# stm32-2inch40-usb-sd-proto.net
KiCad netlist of a schematic drawn in EAGLE
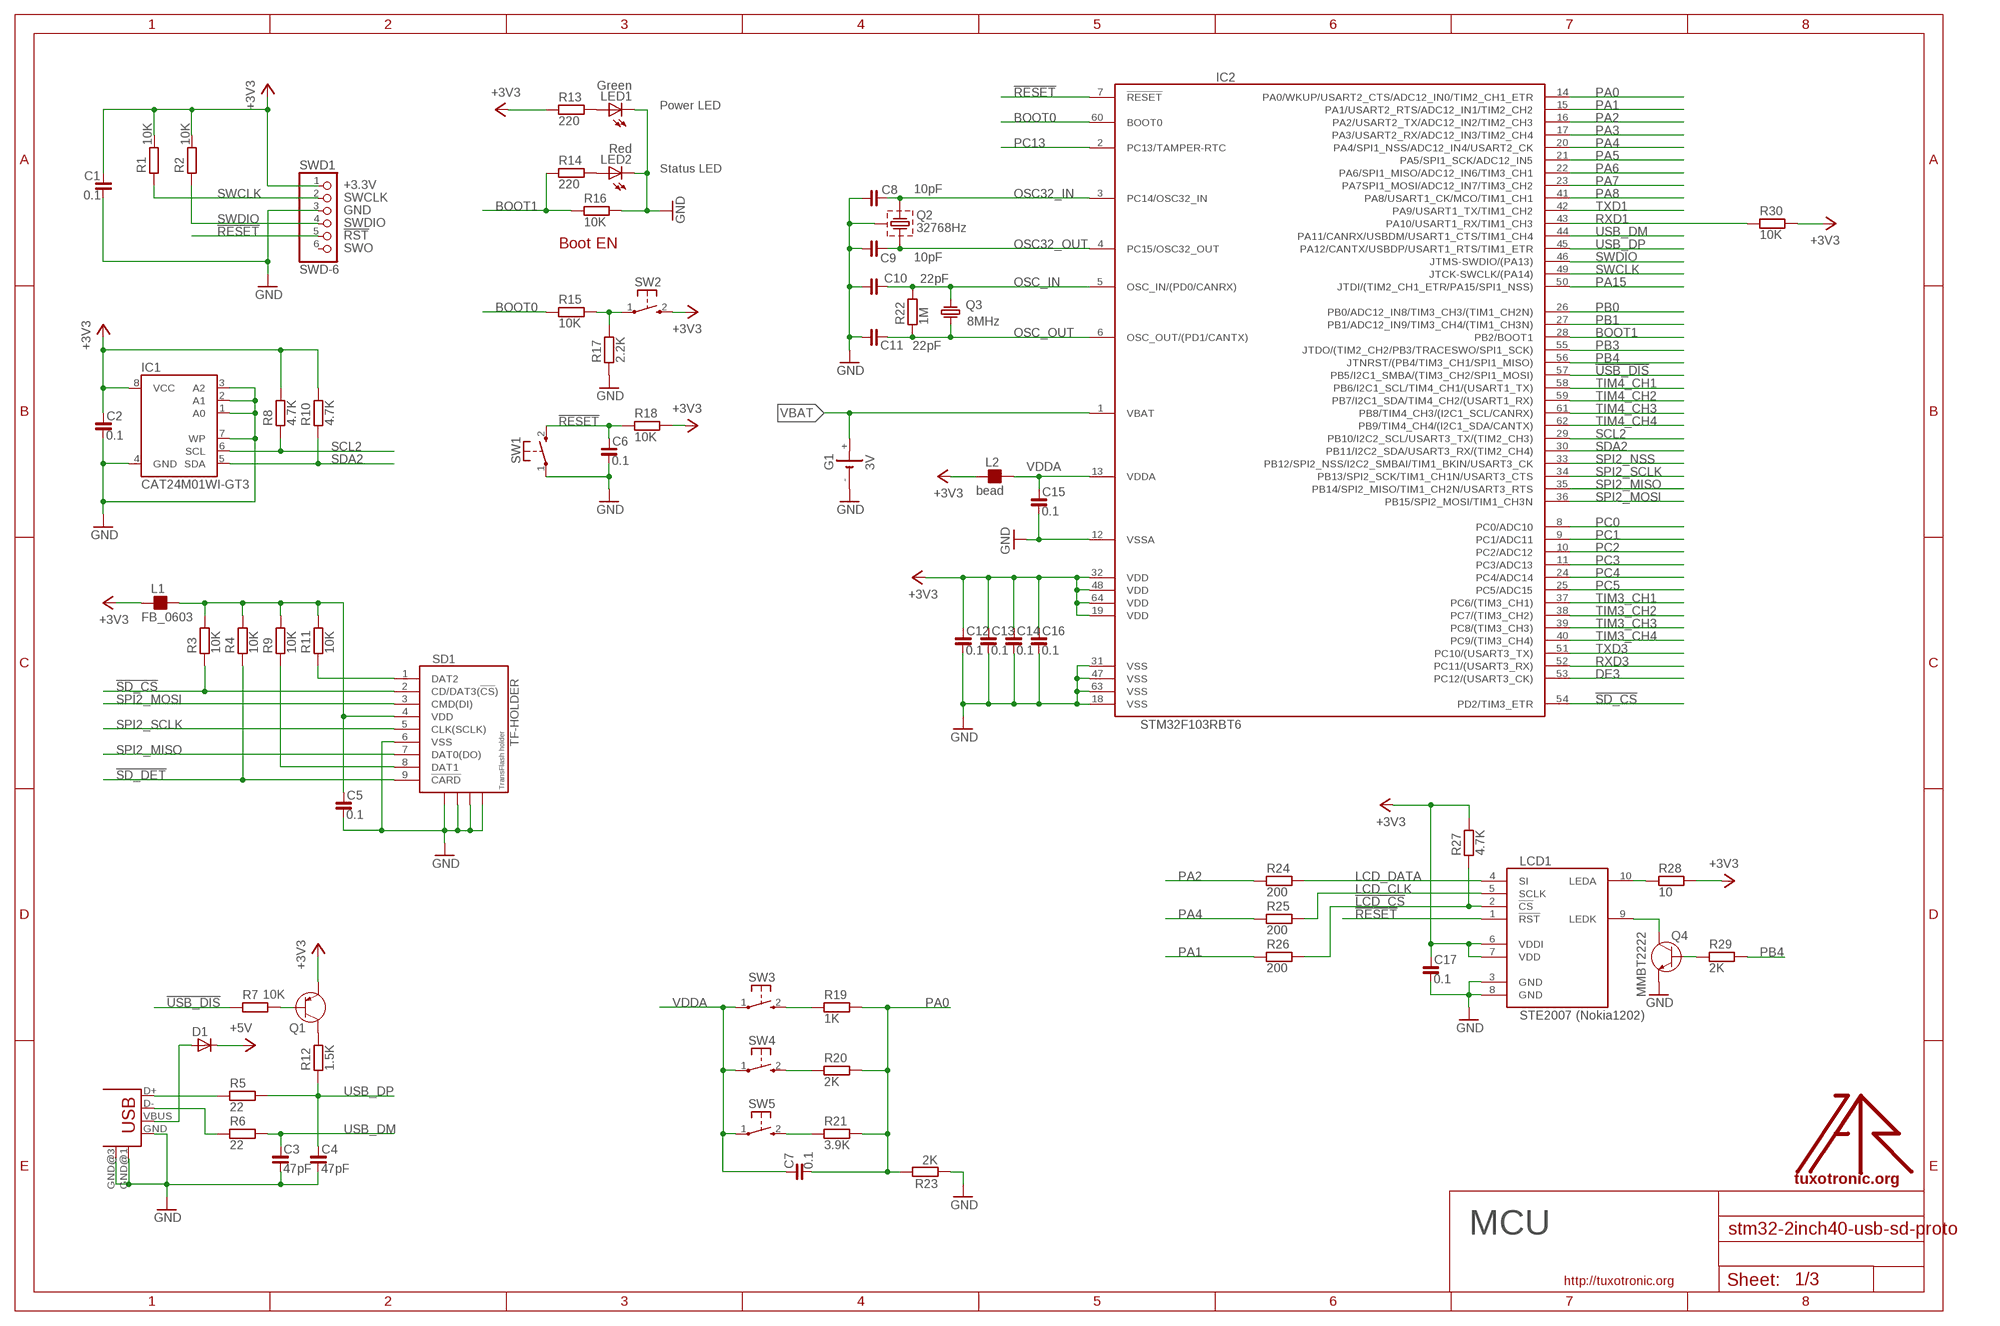
[diagram p0: schematic, sheet 1]
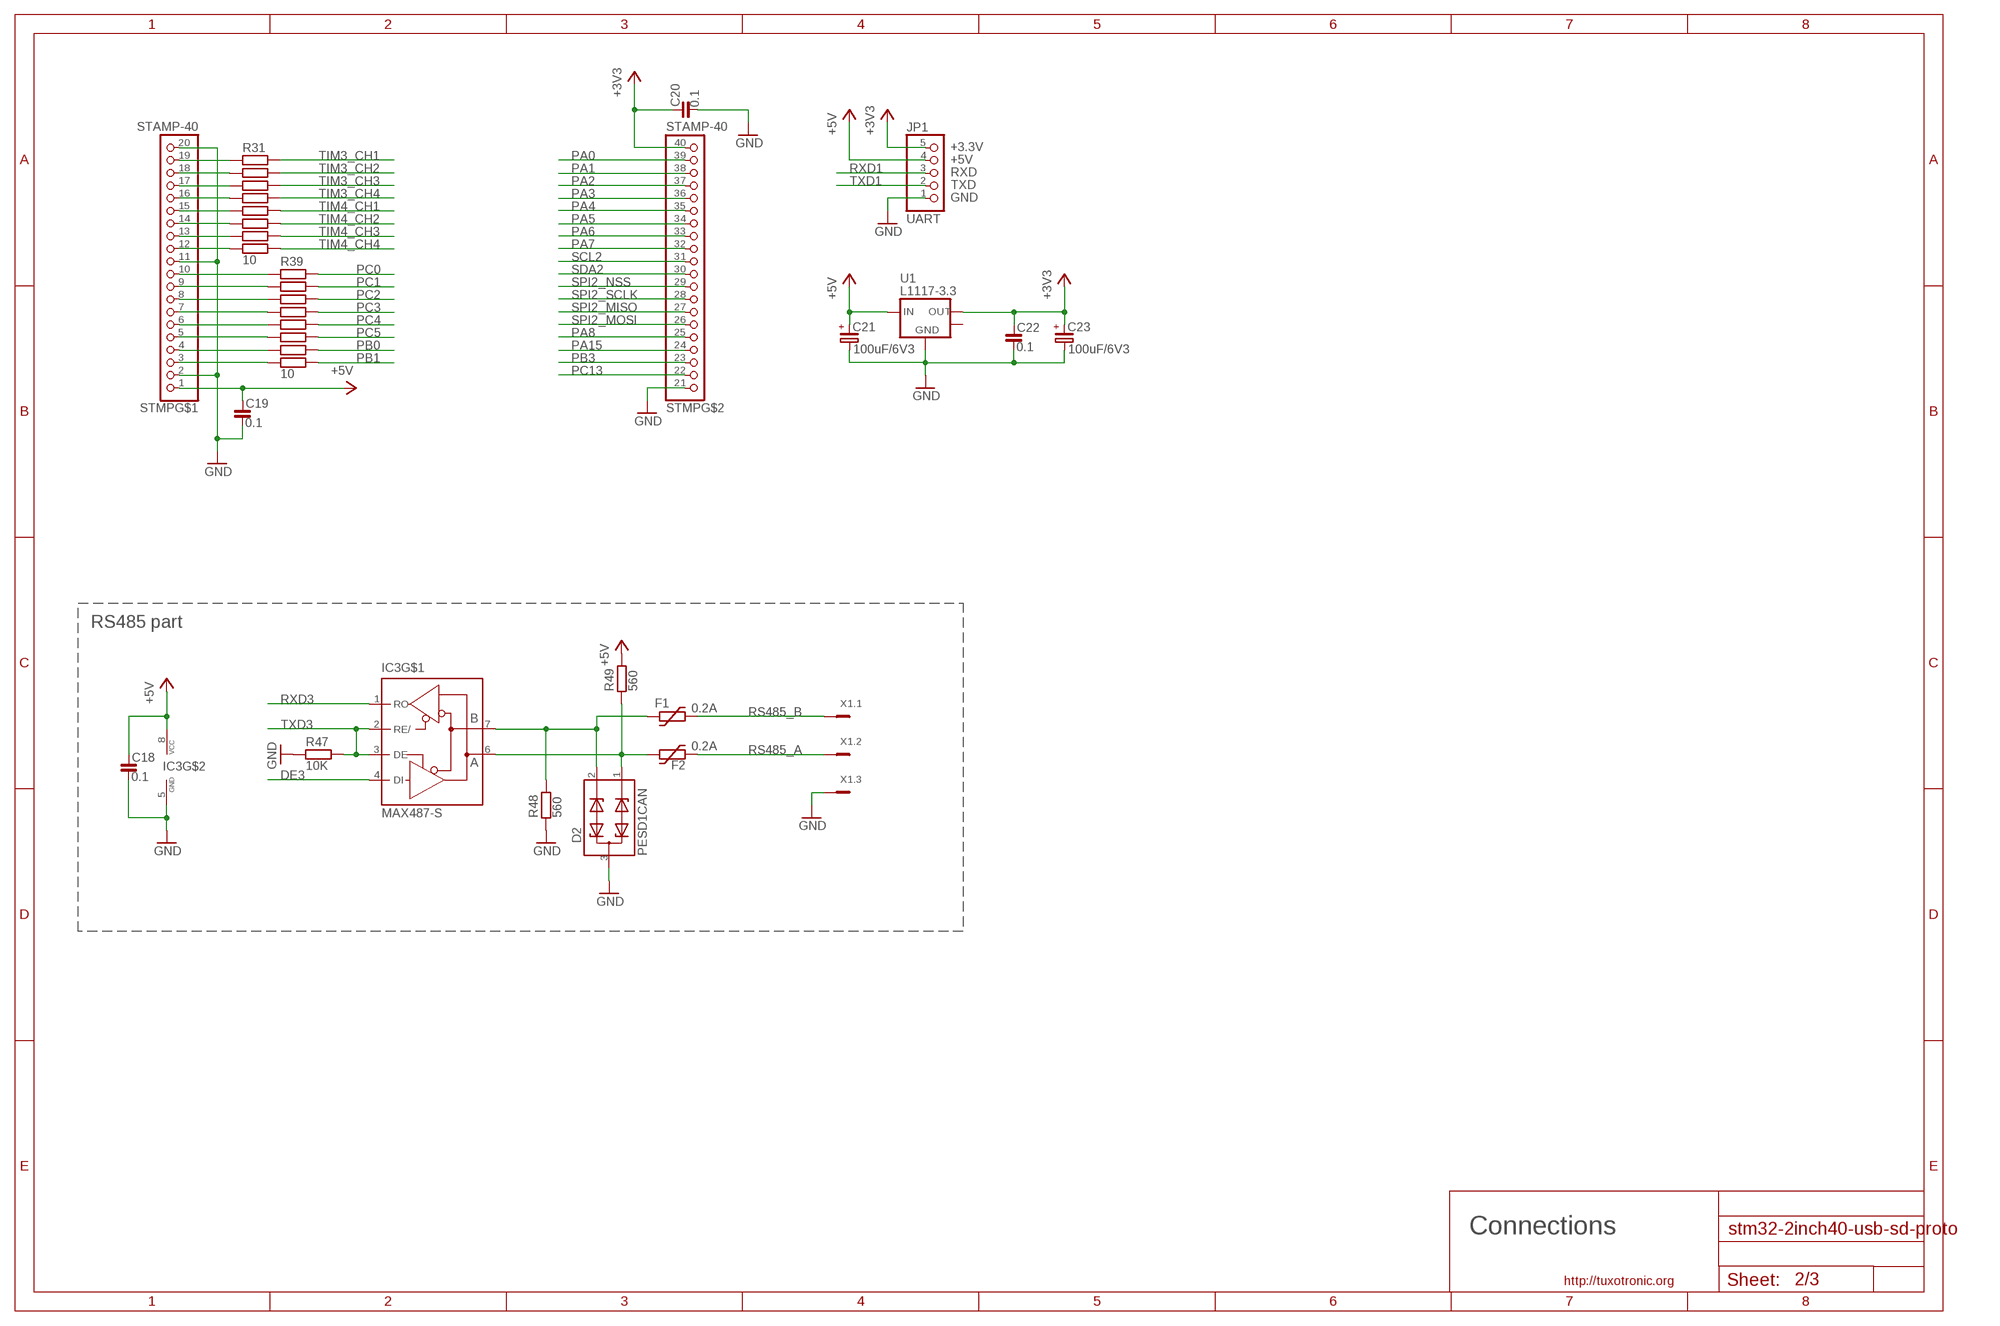
[diagram p1: schematic, sheet 2]
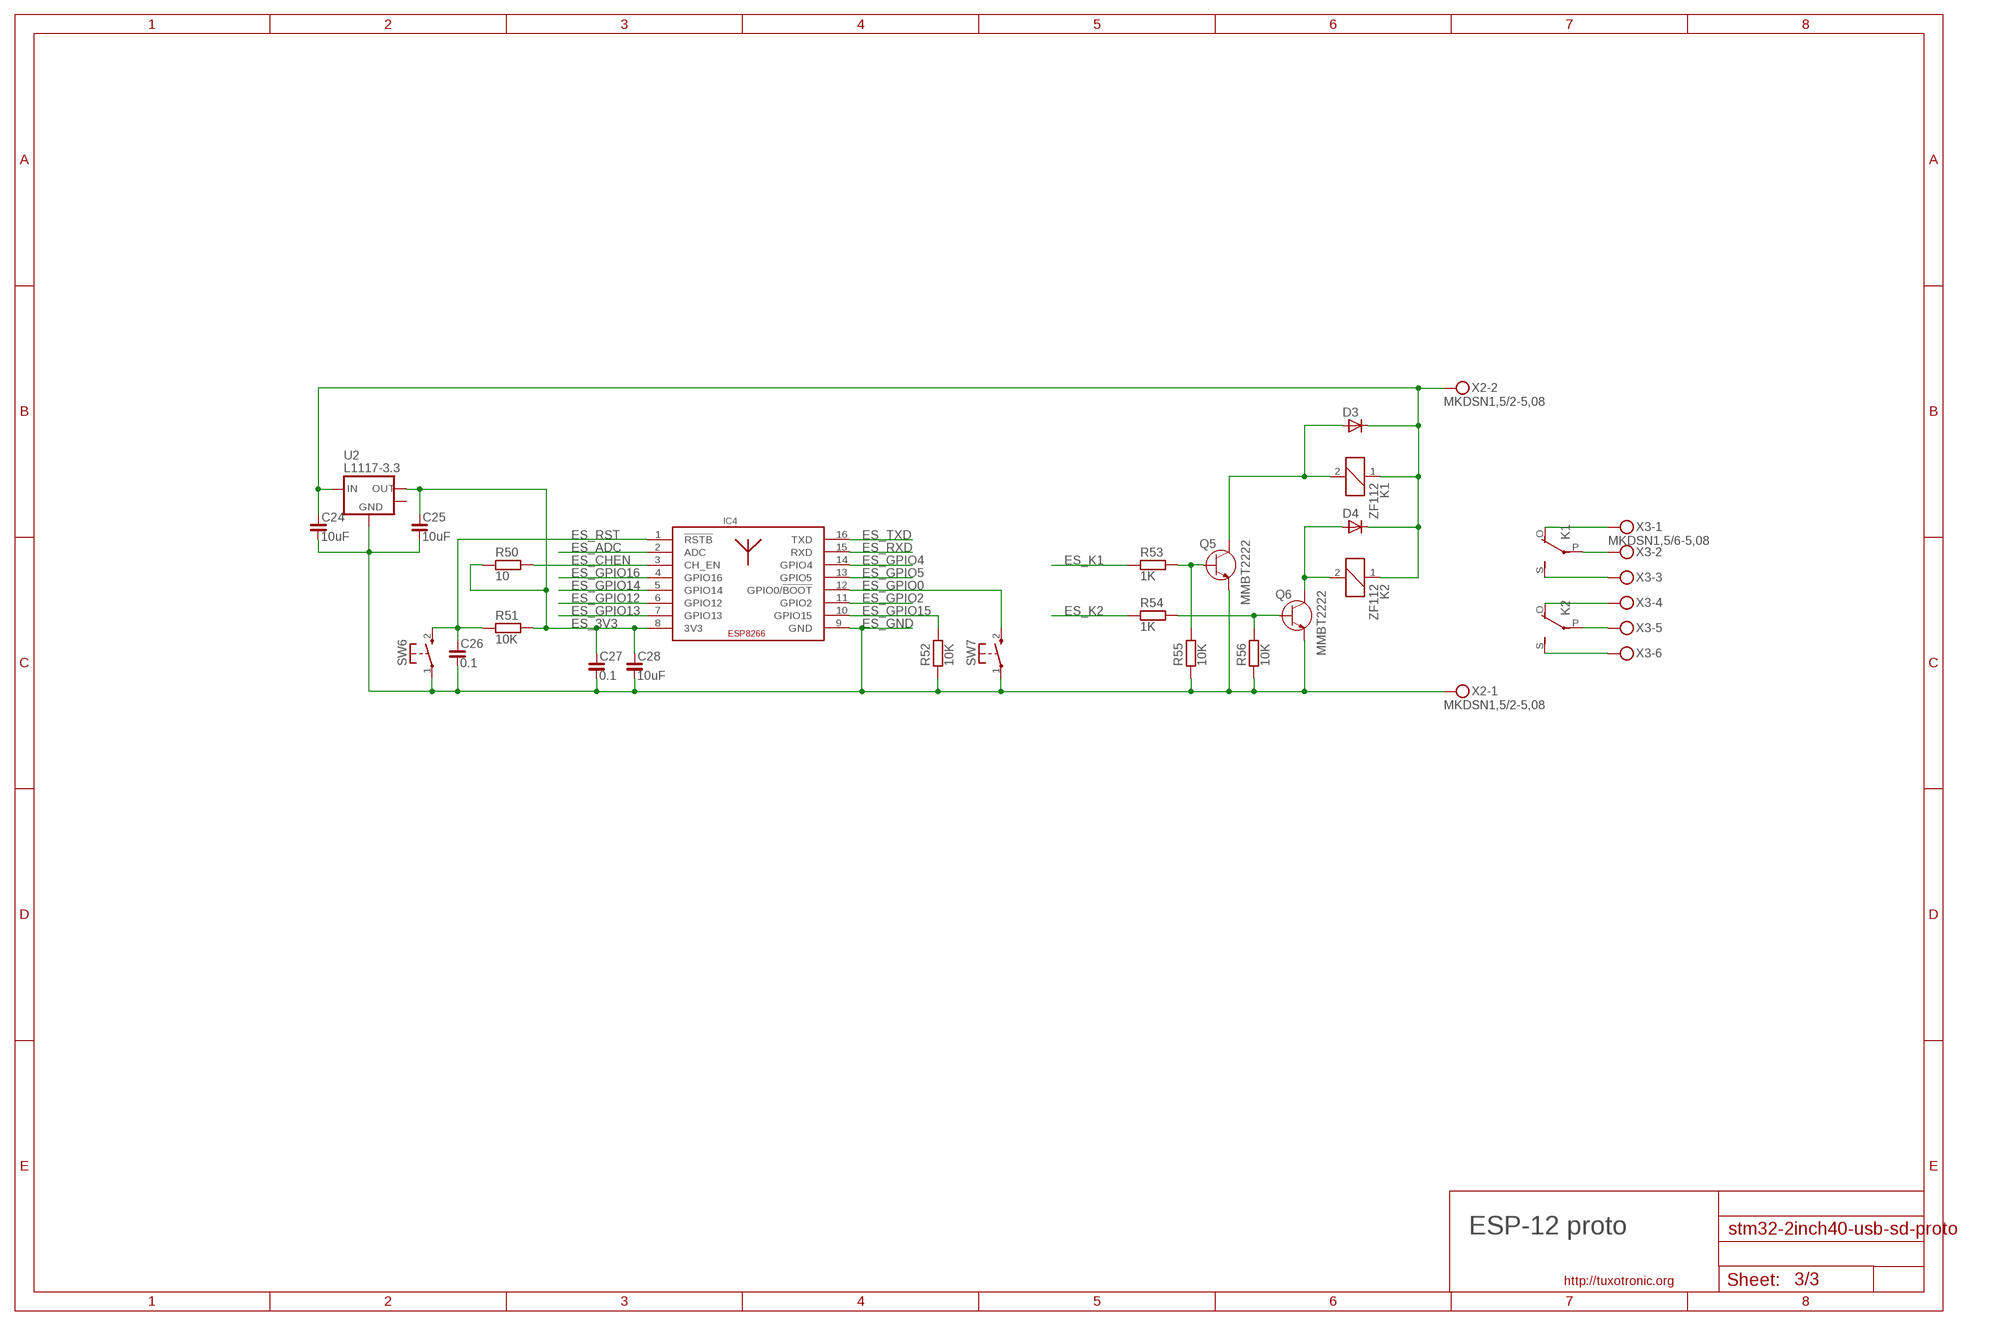
[diagram p2: schematic, sheet 3]

(export (version "E")
  (design (tool "Eeschema 10.0.6"))
  (components
    (comp (ref "C24")
      (value "10uF")
      (footprint "eagle-import:C0805")
      (libsource (lib "eagle-import") (part "C_0805"))
    )
    (comp (ref "C25")
      (value "10uF")
      (footprint "eagle-import:C0805")
      (libsource (lib "eagle-import") (part "C_0805"))
    )
    (comp (ref "C26")
      (value "0.1")
      (footprint "eagle-import:C0805")
      (libsource (lib "eagle-import") (part "C_0805"))
    )
    (comp (ref "C27")
      (value "0.1")
      (footprint "eagle-import:C0805")
      (libsource (lib "eagle-import") (part "C_0805"))
    )
    (comp (ref "C28")
      (value "10uF")
      (footprint "eagle-import:C0805")
      (libsource (lib "eagle-import") (part "C_0805"))
    )
    (comp (ref "D3")
      (value "D-SOD-80")
      (footprint "eagle-import:SOD80")
      (libsource (lib "eagle-import") (part "D-SOD-80"))
    )
    (comp (ref "D4")
      (value "D-SOD-80")
      (footprint "eagle-import:SOD80")
      (libsource (lib "eagle-import") (part "D-SOD-80"))
    )
    (comp (ref "IC4")
      (value "ESP-12")
      (footprint "eagle-import:ESP12")
      (libsource (lib "eagle-import") (part "ESP-12"))
    )
    (comp (ref "K1")
      (value "ZF112")
      (footprint "eagle-import:ZF112")
      (libsource (lib "eagle-import") (part "ZF112"))
    )
    (comp (ref "K2")
      (value "ZF112")
      (footprint "eagle-import:ZF112")
      (libsource (lib "eagle-import") (part "ZF112"))
    )
    (comp (ref "Q5")
      (value "MMBT2222")
      (footprint "eagle-import:SOT23")
      (libsource (lib "eagle-import") (part "MMBT2222"))
    )
    (comp (ref "Q6")
      (value "MMBT2222")
      (footprint "eagle-import:SOT23")
      (libsource (lib "eagle-import") (part "MMBT2222"))
    )
    (comp (ref "R50")
      (value "10")
      (footprint "eagle-import:R0805")
      (libsource (lib "eagle-import") (part "R_0805"))
    )
    (comp (ref "R51")
      (value "10K")
      (footprint "eagle-import:R0805")
      (libsource (lib "eagle-import") (part "R_0805"))
    )
    (comp (ref "R52")
      (value "10K")
      (footprint "eagle-import:R0805")
      (libsource (lib "eagle-import") (part "R_0805"))
    )
    (comp (ref "R53")
      (value "1K")
      (footprint "eagle-import:R0805")
      (libsource (lib "eagle-import") (part "R_0805"))
    )
    (comp (ref "R54")
      (value "1K")
      (footprint "eagle-import:R0805")
      (libsource (lib "eagle-import") (part "R_0805"))
    )
    (comp (ref "R55")
      (value "10K")
      (footprint "eagle-import:R0805")
      (libsource (lib "eagle-import") (part "R_0805"))
    )
    (comp (ref "R56")
      (value "10K")
      (footprint "eagle-import:R0805")
      (libsource (lib "eagle-import") (part "R_0805"))
    )
    (comp (ref "SW6")
      (value "KSS-2EG4430")
      (footprint "eagle-import:KSS-2EG4430")
      (libsource (lib "eagle-import") (part "KSS-2EG4430"))
    )
    (comp (ref "SW7")
      (value "KSS-2EG4430")
      (footprint "eagle-import:KSS-2EG4430")
      (libsource (lib "eagle-import") (part "KSS-2EG4430"))
    )
    (comp (ref "U2")
      (value "L1117-3.3")
      (footprint "eagle-import:SOT223")
      (libsource (lib "eagle-import") (part "LM1117-3.3"))
    )
    (comp (ref "X2")
      (value "MKDSN1,5/2-5,08")
      (footprint "eagle-import:MKDSN1,5_2-5,08")
      (libsource (lib "eagle-import") (part "MKDSN1,5/2-5,08"))
    )
    (comp (ref "X3")
      (value "MKDSN1,5/6-5,08")
      (footprint "eagle-import:MKDSN1,5_6-5,08")
      (libsource (lib "eagle-import") (part "MKDSN1,5/6-5,08"))
    )
    (comp (ref "C18")
      (value "0.1")
      (footprint "eagle-import:C0603")
      (libsource (lib "eagle-import") (part "C_0603"))
    )
    (comp (ref "C19")
      (value "0.1")
      (footprint "eagle-import:C0805")
      (libsource (lib "eagle-import") (part "C_0805"))
    )
    (comp (ref "C20")
      (value "0.1")
      (footprint "eagle-import:C0805")
      (libsource (lib "eagle-import") (part "C_0805"))
    )
    (comp (ref "C21")
      (value "100uF/6V3")
      (footprint "eagle-import:SMC_D")
      (libsource (lib "eagle-import") (part "CP_SMCD"))
    )
    (comp (ref "C22")
      (value "0.1")
      (footprint "eagle-import:C0805")
      (libsource (lib "eagle-import") (part "C_0805"))
    )
    (comp (ref "C23")
      (value "100uF/6V3")
      (footprint "eagle-import:SMC_D")
      (libsource (lib "eagle-import") (part "CP_SMCD"))
    )
    (comp (ref "D2")
      (value "PESD1CAN")
      (footprint "eagle-import:SOT23")
      (libsource (lib "eagle-import") (part "PESD1CAN"))
    )
    (comp (ref "F1")
      (value "0.2A")
      (footprint "eagle-import:1206L")
      (libsource (lib "eagle-import") (part "1206L"))
    )
    (comp (ref "F2")
      (value "0.2A")
      (footprint "eagle-import:1206L")
      (libsource (lib "eagle-import") (part "1206L"))
    )
    (comp (ref "IC3")
      (value "MAX487-S")
      (footprint "eagle-import:SO08")
      (libsource (lib "eagle-import") (part "MAX487-S"))
    )
    (comp (ref "JP1")
      (value "UART")
      (footprint "eagle-import:UART_1X05")
      (libsource (lib "eagle-import") (part "UART-5_2.54"))
    )
    (comp (ref "R31")
      (value "10")
      (footprint "eagle-import:R0603")
      (libsource (lib "eagle-import") (part "R_0603"))
    )
    (comp (ref "R32")
      (value "10")
      (footprint "eagle-import:R0603")
      (libsource (lib "eagle-import") (part "R_0603"))
    )
    (comp (ref "R33")
      (value "10")
      (footprint "eagle-import:R0603")
      (libsource (lib "eagle-import") (part "R_0603"))
    )
    (comp (ref "R34")
      (value "10")
      (footprint "eagle-import:R0603")
      (libsource (lib "eagle-import") (part "R_0603"))
    )
    (comp (ref "R35")
      (value "10")
      (footprint "eagle-import:R0603")
      (libsource (lib "eagle-import") (part "R_0603"))
    )
    (comp (ref "R36")
      (value "10")
      (footprint "eagle-import:R0603")
      (libsource (lib "eagle-import") (part "R_0603"))
    )
    (comp (ref "R37")
      (value "10")
      (footprint "eagle-import:R0603")
      (libsource (lib "eagle-import") (part "R_0603"))
    )
    (comp (ref "R38")
      (value "10")
      (footprint "eagle-import:R0603")
      (libsource (lib "eagle-import") (part "R_0603"))
    )
    (comp (ref "R39")
      (value "10")
      (footprint "eagle-import:R0603")
      (libsource (lib "eagle-import") (part "R_0603"))
    )
    (comp (ref "R40")
      (value "10")
      (footprint "eagle-import:R0603")
      (libsource (lib "eagle-import") (part "R_0603"))
    )
    (comp (ref "R41")
      (value "10")
      (footprint "eagle-import:R0603")
      (libsource (lib "eagle-import") (part "R_0603"))
    )
    (comp (ref "R42")
      (value "10")
      (footprint "eagle-import:R0603")
      (libsource (lib "eagle-import") (part "R_0603"))
    )
    (comp (ref "R43")
      (value "10")
      (footprint "eagle-import:R0603")
      (libsource (lib "eagle-import") (part "R_0603"))
    )
    (comp (ref "R44")
      (value "10")
      (footprint "eagle-import:R0603")
      (libsource (lib "eagle-import") (part "R_0603"))
    )
    (comp (ref "R45")
      (value "10")
      (footprint "eagle-import:R0603")
      (libsource (lib "eagle-import") (part "R_0603"))
    )
    (comp (ref "R46")
      (value "10")
      (footprint "eagle-import:R0603")
      (libsource (lib "eagle-import") (part "R_0603"))
    )
    (comp (ref "R47")
      (value "10K")
      (footprint "eagle-import:R0603")
      (libsource (lib "eagle-import") (part "R_0603"))
    )
    (comp (ref "R48")
      (value "560")
      (footprint "eagle-import:R0603")
      (libsource (lib "eagle-import") (part "R_0603"))
    )
    (comp (ref "R49")
      (value "560")
      (footprint "eagle-import:R0603")
      (libsource (lib "eagle-import") (part "R_0603"))
    )
    (comp (ref "STMP")
      (value "STAMP-40")
      (footprint "eagle-import:STAMP-40")
      (libsource (lib "eagle-import") (part "STAMP-40"))
    )
    (comp (ref "U1")
      (value "L1117-3.3")
      (footprint "eagle-import:SOT223")
      (libsource (lib "eagle-import") (part "LM1117-3.3"))
    )
    (comp (ref "X1")
      (value "MCV3")
      (footprint "eagle-import:MCV3")
      (libsource (lib "eagle-import") (part "MCV3"))
    )
    (comp (ref "C1")
      (value "0.1")
      (footprint "eagle-import:C0603")
      (libsource (lib "eagle-import") (part "C_0603"))
    )
    (comp (ref "C2")
      (value "0.1")
      (footprint "eagle-import:C0603")
      (libsource (lib "eagle-import") (part "C_0603"))
    )
    (comp (ref "C3")
      (value "47pF")
      (footprint "eagle-import:C0603")
      (libsource (lib "eagle-import") (part "C_0603"))
    )
    (comp (ref "C4")
      (value "47pF")
      (footprint "eagle-import:C0603")
      (libsource (lib "eagle-import") (part "C_0603"))
    )
    (comp (ref "C5")
      (value "0.1")
      (footprint "eagle-import:C0603")
      (libsource (lib "eagle-import") (part "C_0603"))
    )
    (comp (ref "C6")
      (value "0.1")
      (footprint "eagle-import:C0603")
      (libsource (lib "eagle-import") (part "C_0603"))
    )
    (comp (ref "C7")
      (value "0.1")
      (footprint "eagle-import:C0603")
      (libsource (lib "eagle-import") (part "C_0603"))
    )
    (comp (ref "C8")
      (value "10pF")
      (footprint "eagle-import:C0603")
      (libsource (lib "eagle-import") (part "C_0603"))
    )
    (comp (ref "C9")
      (value "10pF")
      (footprint "eagle-import:C0603")
      (libsource (lib "eagle-import") (part "C_0603"))
    )
    (comp (ref "C10")
      (value "22pF")
      (footprint "eagle-import:C0603")
      (libsource (lib "eagle-import") (part "C_0603"))
    )
    (comp (ref "C11")
      (value "22pF")
      (footprint "eagle-import:C0603")
      (libsource (lib "eagle-import") (part "C_0603"))
    )
    (comp (ref "C12")
      (value "0.1")
      (footprint "eagle-import:C0603")
      (libsource (lib "eagle-import") (part "C_0603"))
    )
    (comp (ref "C13")
      (value "0.1")
      (footprint "eagle-import:C0603")
      (libsource (lib "eagle-import") (part "C_0603"))
    )
    (comp (ref "C14")
      (value "0.1")
      (footprint "eagle-import:C0603")
      (libsource (lib "eagle-import") (part "C_0603"))
    )
    (comp (ref "C15")
      (value "0.1")
      (footprint "eagle-import:C0603")
      (libsource (lib "eagle-import") (part "C_0603"))
    )
    (comp (ref "C16")
      (value "0.1")
      (footprint "eagle-import:C0603")
      (libsource (lib "eagle-import") (part "C_0603"))
    )
    (comp (ref "C17")
      (value "0.1")
      (footprint "eagle-import:C0603")
      (libsource (lib "eagle-import") (part "C_0603"))
    )
    (comp (ref "D1")
      (value "D-SOD-87")
      (footprint "eagle-import:SOD87")
      (libsource (lib "eagle-import") (part "D-SOD-87"))
    )
    (comp (ref "G1")
      (value "3V")
      (footprint "eagle-import:SMT1220")
      (libsource (lib "eagle-import") (part "1220SMT"))
    )
    (comp (ref "IC1")
      (value "CAT24M01WI-GT3")
      (footprint "eagle-import:SO08")
      (libsource (lib "eagle-import") (part "AT24CS256"))
    )
    (comp (ref "IC2")
      (value "STM32F103RBT6")
      (footprint "eagle-import:TQFP64")
      (libsource (lib "eagle-import") (part "STM32F103R"))
    )
    (comp (ref "L1")
      (value "FB_0603")
      (footprint "eagle-import:L0603")
      (libsource (lib "eagle-import") (part "FB_0603"))
    )
    (comp (ref "L2")
      (value "bead")
      (footprint "eagle-import:L0603")
      (libsource (lib "eagle-import") (part "FB_0603"))
    )
    (comp (ref "LCD1")
      (value "STE2007 (Nokia1202)")
      (footprint "eagle-import:NOKIA1202LCD-EXT")
      (libsource (lib "eagle-import") (part "LCD1202-EXT"))
    )
    (comp (ref "LED1")
      (value "Green")
      (footprint "eagle-import:CHIP-LED0805")
      (libsource (lib "eagle-import") (part "LEDCHIP-LED0805"))
    )
    (comp (ref "LED2")
      (value "Red")
      (footprint "eagle-import:CHIP-LED0805")
      (libsource (lib "eagle-import") (part "LEDCHIP-LED0805"))
    )
    (comp (ref "LOGO1")
      (value "LOGO")
      (footprint "eagle-import:TT_LOGO")
      (libsource (lib "eagle-import") (part "LOGO"))
    )
    (comp (ref "Q1")
      (value "PNP-SOT23")
      (footprint "eagle-import:SOT23")
      (libsource (lib "eagle-import") (part "PNP-SOT23"))
    )
    (comp (ref "Q2")
      (value "32768Hz")
      (footprint "eagle-import:TC38H-G")
      (libsource (lib "eagle-import") (part "CRSTL3-"))
    )
    (comp (ref "Q3")
      (value "8MHz")
      (footprint "eagle-import:HC49_S")
      (libsource (lib "eagle-import") (part "CRYSTAL-HC49S"))
    )
    (comp (ref "Q4")
      (value "MMBT2222")
      (footprint "eagle-import:SOT23")
      (libsource (lib "eagle-import") (part "MMBT2222"))
    )
    (comp (ref "R1")
      (value "10K")
      (footprint "eagle-import:R0603")
      (libsource (lib "eagle-import") (part "R_0603"))
    )
    (comp (ref "R2")
      (value "10K")
      (footprint "eagle-import:R0603")
      (libsource (lib "eagle-import") (part "R_0603"))
    )
    (comp (ref "R3")
      (value "10K")
      (footprint "eagle-import:R0603")
      (libsource (lib "eagle-import") (part "R_0603"))
    )
    (comp (ref "R4")
      (value "10K")
      (footprint "eagle-import:R0603")
      (libsource (lib "eagle-import") (part "R_0603"))
    )
    (comp (ref "R5")
      (value "22")
      (footprint "eagle-import:R0603")
      (libsource (lib "eagle-import") (part "R_0603"))
    )
    (comp (ref "R6")
      (value "22")
      (footprint "eagle-import:R0603")
      (libsource (lib "eagle-import") (part "R_0603"))
    )
    (comp (ref "R7")
      (value "10K")
      (footprint "eagle-import:R0603")
      (libsource (lib "eagle-import") (part "R_0603"))
    )
    (comp (ref "R8")
      (value "4.7K")
      (footprint "eagle-import:R0603")
      (libsource (lib "eagle-import") (part "R_0603"))
    )
    (comp (ref "R9")
      (value "10K")
      (footprint "eagle-import:R0603")
      (libsource (lib "eagle-import") (part "R_0603"))
    )
    (comp (ref "R10")
      (value "4.7K")
      (footprint "eagle-import:R0603")
      (libsource (lib "eagle-import") (part "R_0603"))
    )
    (comp (ref "R11")
      (value "10K")
      (footprint "eagle-import:R0603")
      (libsource (lib "eagle-import") (part "R_0603"))
    )
    (comp (ref "R12")
      (value "1.5K")
      (footprint "eagle-import:R0603")
      (libsource (lib "eagle-import") (part "R_0603"))
    )
    (comp (ref "R13")
      (value "220")
      (footprint "eagle-import:R0603")
      (libsource (lib "eagle-import") (part "R_0603"))
    )
    (comp (ref "R14")
      (value "220")
      (footprint "eagle-import:R0603")
      (libsource (lib "eagle-import") (part "R_0603"))
    )
    (comp (ref "R15")
      (value "10K")
      (footprint "eagle-import:R0603")
      (libsource (lib "eagle-import") (part "R_0603"))
    )
    (comp (ref "R16")
      (value "10K")
      (footprint "eagle-import:R0603")
      (libsource (lib "eagle-import") (part "R_0603"))
    )
    (comp (ref "R17")
      (value "2.2K")
      (footprint "eagle-import:R0603")
      (libsource (lib "eagle-import") (part "R_0603"))
    )
    (comp (ref "R18")
      (value "10K")
      (footprint "eagle-import:R0603")
      (libsource (lib "eagle-import") (part "R_0603"))
    )
    (comp (ref "R19")
      (value "1K")
      (footprint "eagle-import:R0603")
      (libsource (lib "eagle-import") (part "R_0603"))
    )
    (comp (ref "R20")
      (value "2K")
      (footprint "eagle-import:R0603")
      (libsource (lib "eagle-import") (part "R_0603"))
    )
    (comp (ref "R21")
      (value "3.9K")
      (footprint "eagle-import:R0603")
      (libsource (lib "eagle-import") (part "R_0603"))
    )
    (comp (ref "R22")
      (value "1M")
      (footprint "eagle-import:R0603")
      (libsource (lib "eagle-import") (part "R_0603"))
    )
    (comp (ref "R23")
      (value "2K")
      (footprint "eagle-import:R0603")
      (libsource (lib "eagle-import") (part "R_0603"))
    )
    (comp (ref "R24")
      (value "200")
      (footprint "eagle-import:R0603")
      (libsource (lib "eagle-import") (part "R_0603"))
    )
    (comp (ref "R25")
      (value "200")
      (footprint "eagle-import:R0603")
      (libsource (lib "eagle-import") (part "R_0603"))
    )
    (comp (ref "R26")
      (value "200")
      (footprint "eagle-import:R0603")
      (libsource (lib "eagle-import") (part "R_0603"))
    )
    (comp (ref "R27")
      (value "4.7K")
      (footprint "eagle-import:R0603")
      (libsource (lib "eagle-import") (part "R_0603"))
    )
    (comp (ref "R28")
      (value "10")
      (footprint "eagle-import:R0603")
      (libsource (lib "eagle-import") (part "R_0603"))
    )
    (comp (ref "R29")
      (value "2K")
      (footprint "eagle-import:R0603")
      (libsource (lib "eagle-import") (part "R_0603"))
    )
    (comp (ref "R30")
      (value "10K")
      (footprint "eagle-import:R0603")
      (libsource (lib "eagle-import") (part "R_0603"))
    )
    (comp (ref "SD1")
      (value "TF-HOLDER")
      (footprint "eagle-import:TF-PULL")
      (libsource (lib "eagle-import") (part "TF-HOLDER"))
    )
    (comp (ref "SW1")
      (value "KSS-2EG4430")
      (footprint "eagle-import:KSS-2EG4430")
      (libsource (lib "eagle-import") (part "KSS-2EG4430"))
    )
    (comp (ref "SW2")
      (value "KSS-2EG4430")
      (footprint "eagle-import:KSS-2EG4430")
      (libsource (lib "eagle-import") (part "KSS-2EG4430"))
    )
    (comp (ref "SW3")
      (value "KSS-2EG4430")
      (footprint "eagle-import:KSS-2EG4430")
      (libsource (lib "eagle-import") (part "KSS-2EG4430"))
    )
    (comp (ref "SW4")
      (value "KSS-2EG4430")
      (footprint "eagle-import:KSS-2EG4430")
      (libsource (lib "eagle-import") (part "KSS-2EG4430"))
    )
    (comp (ref "SW5")
      (value "KSS-2EG4430")
      (footprint "eagle-import:KSS-2EG4430")
      (libsource (lib "eagle-import") (part "KSS-2EG4430"))
    )
    (comp (ref "SWD1")
      (value "SWD-6")
      (footprint "eagle-import:JTAG6PIN")
      (libsource (lib "eagle-import") (part "SWD-6"))
    )
    (comp (ref "USB1")
      (value "USB-MB-S")
      (footprint "eagle-import:USB-MB-S")
      (libsource (lib "eagle-import") (part "USB-MB-S"))
    )
  )
  (nets
    (net (code "1") (name "+3V3") (class "Default")
      (node (ref "C1") (pin "1") (pinfunction "1_1") (pintype "passive"))
      (node (ref "C12") (pin "1") (pinfunction "1_1") (pintype "passive"))
      (node (ref "C13") (pin "1") (pinfunction "1_1") (pintype "passive"))
      (node (ref "C14") (pin "1") (pinfunction "1_1") (pintype "passive"))
      (node (ref "C16") (pin "1") (pinfunction "1_1") (pintype "passive"))
      (node (ref "C17") (pin "1") (pinfunction "1_1") (pintype "passive"))
      (node (ref "C2") (pin "1") (pinfunction "1_1") (pintype "passive"))
      (node (ref "C20") (pin "1") (pinfunction "1_1") (pintype "passive"))
      (node (ref "C22") (pin "1") (pinfunction "1_1") (pintype "passive"))
      (node (ref "C23") (pin "+") (pinfunction "+_+") (pintype "passive"))
      (node (ref "IC1") (pin "8") (pinfunction "VCC_8") (pintype "power_in"))
      (node (ref "IC2") (pin "19") (pinfunction "VDD_19") (pintype "power_in"))
      (node (ref "IC2") (pin "32") (pinfunction "VDD_32") (pintype "power_in"))
      (node (ref "IC2") (pin "48") (pinfunction "VDD_48") (pintype "power_in"))
      (node (ref "IC2") (pin "64") (pinfunction "VDD_64") (pintype "power_in"))
      (node (ref "JP1") (pin "5") (pinfunction "5_5") (pintype "passive"))
      (node (ref "L1") (pin "1") (pinfunction "1_1") (pintype "passive"))
      (node (ref "L2") (pin "1") (pinfunction "1_1") (pintype "passive"))
      (node (ref "LCD1") (pin "6") (pinfunction "VDDI_6") (pintype "power_in"))
      (node (ref "LCD1") (pin "7") (pinfunction "VDD_7") (pintype "power_in"))
      (node (ref "Q1") (pin "2") (pinfunction "E_2") (pintype "passive"))
      (node (ref "R1") (pin "2") (pinfunction "2_2") (pintype "passive"))
      (node (ref "R10") (pin "2") (pinfunction "2_2") (pintype "passive"))
      (node (ref "R13") (pin "1") (pinfunction "1_1") (pintype "passive"))
      (node (ref "R18") (pin "2") (pinfunction "2_2") (pintype "passive"))
      (node (ref "R2") (pin "2") (pinfunction "2_2") (pintype "passive"))
      (node (ref "R27") (pin "2") (pinfunction "2_2") (pintype "passive"))
      (node (ref "R28") (pin "2") (pinfunction "2_2") (pintype "passive"))
      (node (ref "R30") (pin "2") (pinfunction "2_2") (pintype "passive"))
      (node (ref "R8") (pin "2") (pinfunction "2_2") (pintype "passive"))
      (node (ref "STMP") (pin "40") (pinfunction "20_40") (pintype "passive"))
      (node (ref "SW2") (pin "2") (pinfunction "S_2") (pintype "passive"))
      (node (ref "SWD1") (pin "1") (pinfunction "1_1") (pintype "passive"))
      (node (ref "U1") (pin "2") (pinfunction "OUT_2") (pintype "power_in"))
    )
    (net (code "2") (name "+5V") (class "Default")
      (node (ref "C18") (pin "1") (pinfunction "1_1") (pintype "passive"))
      (node (ref "C19") (pin "1") (pinfunction "1_1") (pintype "passive"))
      (node (ref "C21") (pin "+") (pinfunction "+_+") (pintype "passive"))
      (node (ref "D1") (pin "1") (pinfunction "C_1") (pintype "passive"))
      (node (ref "IC3") (pin "8") (pinfunction "VCC_8") (pintype "power_in"))
      (node (ref "JP1") (pin "4") (pinfunction "4_4") (pintype "passive"))
      (node (ref "R49") (pin "2") (pinfunction "2_2") (pintype "passive"))
      (node (ref "STMP") (pin "1") (pinfunction "1_1") (pintype "passive"))
      (node (ref "U1") (pin "3") (pinfunction "IN_3") (pintype "power_in"))
    )
    (net (code "3") (name "BOOT0") (class "Default")
      (node (ref "IC2") (pin "60") (pinfunction "BOOT0_60") (pintype "input"))
      (node (ref "R15") (pin "1") (pinfunction "1_1") (pintype "passive"))
    )
    (net (code "4") (name "BOOT1") (class "Default")
      (node (ref "IC2") (pin "28") (pinfunction "PB2/BOOT1_28") (pintype "bidirectional"))
      (node (ref "R14") (pin "1") (pinfunction "1_1") (pintype "passive"))
      (node (ref "R16") (pin "1") (pinfunction "1_1") (pintype "passive"))
    )
    (net (code "5") (name "DE3") (class "Default")
      (node (ref "IC2") (pin "53") (pinfunction "PC12/(USART3_CK)_53") (pintype "bidirectional"))
      (node (ref "IC3") (pin "4") (pinfunction "DI_4") (pintype "input"))
    )
    (net (code "6") (name "ES_3V3") (class "Default")
      (node (ref "C25") (pin "1") (pinfunction "1_1") (pintype "passive"))
      (node (ref "C27") (pin "1") (pinfunction "1_1") (pintype "passive"))
      (node (ref "C28") (pin "1") (pinfunction "1_1") (pintype "passive"))
      (node (ref "IC4") (pin "8") (pinfunction "3V3_8") (pintype "power_in"))
      (node (ref "R50") (pin "1") (pinfunction "1_1") (pintype "passive"))
      (node (ref "R51") (pin "2") (pinfunction "2_2") (pintype "passive"))
      (node (ref "U2") (pin "2") (pinfunction "OUT_2") (pintype "power_in"))
    )
    (net (code "7") (name "ES_ADC") (class "Default")
      (node (ref "IC4") (pin "2") (pinfunction "ADC_2") (pintype "input"))
    )
    (net (code "8") (name "ES_CHEN") (class "Default")
      (node (ref "IC4") (pin "3") (pinfunction "CH_EN_3") (pintype "input"))
      (node (ref "R50") (pin "2") (pinfunction "2_2") (pintype "passive"))
    )
    (net (code "9") (name "ES_GND") (class "Default")
      (node (ref "C24") (pin "2") (pinfunction "2_2") (pintype "passive"))
      (node (ref "C25") (pin "2") (pinfunction "2_2") (pintype "passive"))
      (node (ref "C26") (pin "2") (pinfunction "2_2") (pintype "passive"))
      (node (ref "C27") (pin "2") (pinfunction "2_2") (pintype "passive"))
      (node (ref "C28") (pin "2") (pinfunction "2_2") (pintype "passive"))
      (node (ref "IC4") (pin "9") (pinfunction "GND_9") (pintype "power_in"))
      (node (ref "Q5") (pin "2") (pinfunction "E_2") (pintype "passive"))
      (node (ref "Q6") (pin "2") (pinfunction "E_2") (pintype "passive"))
      (node (ref "R52") (pin "1") (pinfunction "1_1") (pintype "passive"))
      (node (ref "R55") (pin "1") (pinfunction "1_1") (pintype "passive"))
      (node (ref "R56") (pin "1") (pinfunction "1_1") (pintype "passive"))
      (node (ref "SW6") (pin "1") (pinfunction "P_1") (pintype "passive"))
      (node (ref "SW7") (pin "1") (pinfunction "P_1") (pintype "passive"))
      (node (ref "U2") (pin "1") (pinfunction "GND_1") (pintype "power_in"))
      (node (ref "X2") (pin "1") (pinfunction "KL_1") (pintype "passive"))
    )
    (net (code "10") (name "ES_GPIO0") (class "Default")
      (node (ref "IC4") (pin "12") (pinfunction "GPIO0/~{BOOT}_12") (pintype "bidirectional"))
      (node (ref "SW7") (pin "2") (pinfunction "S_2") (pintype "passive"))
    )
    (net (code "11") (name "ES_GPIO2") (class "Default")
      (node (ref "IC4") (pin "11") (pinfunction "GPIO2_11") (pintype "bidirectional"))
    )
    (net (code "12") (name "ES_GPIO4") (class "Default")
      (node (ref "IC4") (pin "14") (pinfunction "GPIO4_14") (pintype "bidirectional"))
    )
    (net (code "13") (name "ES_GPIO5") (class "Default")
      (node (ref "IC4") (pin "13") (pinfunction "GPIO5_13") (pintype "bidirectional"))
    )
    (net (code "14") (name "ES_GPIO12") (class "Default")
      (node (ref "IC4") (pin "6") (pinfunction "GPIO12_6") (pintype "bidirectional"))
    )
    (net (code "15") (name "ES_GPIO13") (class "Default")
      (node (ref "IC4") (pin "7") (pinfunction "GPIO13_7") (pintype "bidirectional"))
    )
    (net (code "16") (name "ES_GPIO14") (class "Default")
      (node (ref "IC4") (pin "5") (pinfunction "GPIO14_5") (pintype "bidirectional"))
    )
    (net (code "17") (name "ES_GPIO15") (class "Default")
      (node (ref "IC4") (pin "10") (pinfunction "GPIO15_10") (pintype "bidirectional"))
      (node (ref "R52") (pin "2") (pinfunction "2_2") (pintype "passive"))
    )
    (net (code "18") (name "ES_GPIO16") (class "Default")
      (node (ref "IC4") (pin "4") (pinfunction "GPIO16_4") (pintype "bidirectional"))
    )
    (net (code "19") (name "ES_K1") (class "Default")
      (node (ref "R53") (pin "1") (pinfunction "1_1") (pintype "passive"))
    )
    (net (code "20") (name "ES_K2") (class "Default")
      (node (ref "R54") (pin "1") (pinfunction "1_1") (pintype "passive"))
    )
    (net (code "21") (name "ES_RST") (class "Default")
      (node (ref "C26") (pin "1") (pinfunction "1_1") (pintype "passive"))
      (node (ref "IC4") (pin "1") (pinfunction "~{RSTB}_1") (pintype "input"))
      (node (ref "R51") (pin "1") (pinfunction "1_1") (pintype "passive"))
      (node (ref "SW6") (pin "2") (pinfunction "S_2") (pintype "passive"))
    )
    (net (code "22") (name "ES_RXD") (class "Default")
      (node (ref "IC4") (pin "15") (pinfunction "RXD_15") (pintype "input"))
    )
    (net (code "23") (name "ES_TXD") (class "Default")
      (node (ref "IC4") (pin "16") (pinfunction "TXD_16") (pintype "output"))
    )
    (net (code "24") (name "GND") (class "Default")
      (node (ref "C1") (pin "2") (pinfunction "2_2") (pintype "passive"))
      (node (ref "C10") (pin "2") (pinfunction "2_2") (pintype "passive"))
      (node (ref "C11") (pin "2") (pinfunction "2_2") (pintype "passive"))
      (node (ref "C12") (pin "2") (pinfunction "2_2") (pintype "passive"))
      (node (ref "C13") (pin "2") (pinfunction "2_2") (pintype "passive"))
      (node (ref "C14") (pin "2") (pinfunction "2_2") (pintype "passive"))
      (node (ref "C15") (pin "2") (pinfunction "2_2") (pintype "passive"))
      (node (ref "C16") (pin "2") (pinfunction "2_2") (pintype "passive"))
      (node (ref "C17") (pin "2") (pinfunction "2_2") (pintype "passive"))
      (node (ref "C18") (pin "2") (pinfunction "2_2") (pintype "passive"))
      (node (ref "C19") (pin "2") (pinfunction "2_2") (pintype "passive"))
      (node (ref "C2") (pin "2") (pinfunction "2_2") (pintype "passive"))
      (node (ref "C20") (pin "2") (pinfunction "2_2") (pintype "passive"))
      (node (ref "C21") (pin "-") (pinfunction "-_-") (pintype "passive"))
      (node (ref "C22") (pin "2") (pinfunction "2_2") (pintype "passive"))
      (node (ref "C23") (pin "-") (pinfunction "-_-") (pintype "passive"))
      (node (ref "C3") (pin "2") (pinfunction "2_2") (pintype "passive"))
      (node (ref "C4") (pin "2") (pinfunction "2_2") (pintype "passive"))
      (node (ref "C5") (pin "2") (pinfunction "2_2") (pintype "passive"))
      (node (ref "C6") (pin "2") (pinfunction "2_2") (pintype "passive"))
      (node (ref "C8") (pin "2") (pinfunction "2_2") (pintype "passive"))
      (node (ref "C9") (pin "2") (pinfunction "2_2") (pintype "passive"))
      (node (ref "D2") (pin "3") (pinfunction "3_3") (pintype "passive"))
      (node (ref "G1") (pin "-") (pinfunction "-_-") (pintype "passive"))
      (node (ref "IC1") (pin "1") (pinfunction "A0_1") (pintype "input"))
      (node (ref "IC1") (pin "2") (pinfunction "A1_2") (pintype "input"))
      (node (ref "IC1") (pin "3") (pinfunction "A2_3") (pintype "input"))
      (node (ref "IC1") (pin "4") (pinfunction "GND_4") (pintype "power_in"))
      (node (ref "IC1") (pin "7") (pinfunction "WP_7") (pintype "input"))
      (node (ref "IC2") (pin "12") (pinfunction "VSSA_12") (pintype "power_in"))
      (node (ref "IC2") (pin "18") (pinfunction "VSS_18") (pintype "power_in"))
      (node (ref "IC2") (pin "31") (pinfunction "VSS_31") (pintype "power_in"))
      (node (ref "IC2") (pin "47") (pinfunction "VSS_47") (pintype "power_in"))
      (node (ref "IC2") (pin "63") (pinfunction "VSS_63") (pintype "power_in"))
      (node (ref "IC3") (pin "5") (pinfunction "GND_5") (pintype "power_in"))
      (node (ref "JP1") (pin "1") (pinfunction "1_1") (pintype "passive"))
      (node (ref "LCD1") (pin "3") (pinfunction "GND_3") (pintype "power_in"))
      (node (ref "LCD1") (pin "8") (pinfunction "GND_8") (pintype "power_in"))
      (node (ref "LED1") (pin "C") (pinfunction "C_C") (pintype "passive"))
      (node (ref "LED2") (pin "C") (pinfunction "C_C") (pintype "passive"))
      (node (ref "Q2") (pin "GND") (pinfunction "P$1_GND") (pintype "passive"))
      (node (ref "Q4") (pin "2") (pinfunction "E_2") (pintype "passive"))
      (node (ref "R16") (pin "2") (pinfunction "2_2") (pintype "passive"))
      (node (ref "R17") (pin "1") (pinfunction "1_1") (pintype "passive"))
      (node (ref "R23") (pin "1") (pinfunction "1_1") (pintype "passive"))
      (node (ref "R47") (pin "1") (pinfunction "1_1") (pintype "passive"))
      (node (ref "R48") (pin "1") (pinfunction "1_1") (pintype "passive"))
      (node (ref "SD1") (pin "6") (pinfunction "VSS_6") (pintype "power_in"))
      (node (ref "SD1") (pin "S1") (pinfunction "S1_S1") (pintype "passive"))
      (node (ref "SD1") (pin "S2") (pinfunction "S2_S2") (pintype "passive"))
      (node (ref "SD1") (pin "S3") (pinfunction "S3_S3") (pintype "passive"))
      (node (ref "SD1") (pin "S4") (pinfunction "S4_S4") (pintype "passive"))
      (node (ref "STMP") (pin "11") (pinfunction "11_11") (pintype "passive"))
      (node (ref "STMP") (pin "2") (pinfunction "2_2") (pintype "passive"))
      (node (ref "STMP") (pin "20") (pinfunction "20_20") (pintype "passive"))
      (node (ref "STMP") (pin "21") (pinfunction "1_21") (pintype "passive"))
      (node (ref "SW1") (pin "1") (pinfunction "P_1") (pintype "passive"))
      (node (ref "SWD1") (pin "3") (pinfunction "3_3") (pintype "passive"))
      (node (ref "U1") (pin "1") (pinfunction "GND_1") (pintype "power_in"))
      (node (ref "USB1") (pin "GND") (pinfunction "GND_GND") (pintype "bidirectional"))
      (node (ref "USB1") (pin "GND@1") (pinfunction "GND_GND@1") (pintype "bidirectional"))
      (node (ref "USB1") (pin "GND@3") (pinfunction "GND_GND@3") (pintype "bidirectional"))
      (node (ref "X1") (pin "3") (pinfunction "SK_3") (pintype "passive"))
    )
    (net (code "25") (name "LCD_CLK") (class "Default")
      (node (ref "LCD1") (pin "5") (pinfunction "SCLK_5") (pintype "input"))
      (node (ref "R25") (pin "2") (pinfunction "2_2") (pintype "passive"))
    )
    (net (code "26") (name "LCD_DATA") (class "Default")
      (node (ref "LCD1") (pin "4") (pinfunction "SI_4") (pintype "input"))
      (node (ref "R24") (pin "2") (pinfunction "2_2") (pintype "passive"))
    )
    (net (code "27") (name "Net-(D1-A)") (class "Default")
      (node (ref "D1") (pin "2") (pinfunction "A_2") (pintype "passive"))
      (node (ref "USB1") (pin "VBUS") (pinfunction "VBUS_VBUS") (pintype "bidirectional"))
    )
    (net (code "28") (name "Net-(D3-A)") (class "Default")
      (node (ref "D3") (pin "2") (pinfunction "A_2") (pintype "passive"))
      (node (ref "K1") (pin "2") (pinfunction "2_2") (pintype "passive"))
      (node (ref "Q5") (pin "3") (pinfunction "C_3") (pintype "passive"))
    )
    (net (code "29") (name "Net-(D3-C)") (class "Default")
      (node (ref "C24") (pin "1") (pinfunction "1_1") (pintype "passive"))
      (node (ref "D3") (pin "1") (pinfunction "C_1") (pintype "passive"))
      (node (ref "D4") (pin "1") (pinfunction "C_1") (pintype "passive"))
      (node (ref "K1") (pin "1") (pinfunction "1_1") (pintype "passive"))
      (node (ref "K2") (pin "1") (pinfunction "1_1") (pintype "passive"))
      (node (ref "U2") (pin "3") (pinfunction "IN_3") (pintype "power_in"))
      (node (ref "X2") (pin "2") (pinfunction "KL_2") (pintype "passive"))
    )
    (net (code "30") (name "Net-(D4-A)") (class "Default")
      (node (ref "D4") (pin "2") (pinfunction "A_2") (pintype "passive"))
      (node (ref "K2") (pin "2") (pinfunction "2_2") (pintype "passive"))
      (node (ref "Q6") (pin "3") (pinfunction "C_3") (pintype "passive"))
    )
    (net (code "31") (name "Net-(F1-1)") (class "Default")
      (node (ref "D2") (pin "2") (pinfunction "2_2") (pintype "passive"))
      (node (ref "F1") (pin "P$1") (pinfunction "1_P$1") (pintype "passive"))
      (node (ref "IC3") (pin "7") (pinfunction "B_7") (pintype "passive"))
      (node (ref "R48") (pin "2") (pinfunction "2_2") (pintype "passive"))
    )
    (net (code "32") (name "Net-(F2-1)") (class "Default")
      (node (ref "D2") (pin "1") (pinfunction "1_1") (pintype "passive"))
      (node (ref "F2") (pin "P$1") (pinfunction "1_P$1") (pintype "passive"))
      (node (ref "IC3") (pin "6") (pinfunction "A_6") (pintype "passive"))
      (node (ref "R49") (pin "1") (pinfunction "1_1") (pintype "passive"))
    )
    (net (code "33") (name "Net-(LCD1-LEDA)") (class "Default")
      (node (ref "LCD1") (pin "10") (pinfunction "LEDA_10") (pintype "passive"))
      (node (ref "R28") (pin "1") (pinfunction "1_1") (pintype "passive"))
    )
    (net (code "34") (name "Net-(LCD1-LEDK)") (class "Default")
      (node (ref "LCD1") (pin "9") (pinfunction "LEDK_9") (pintype "passive"))
      (node (ref "Q4") (pin "3") (pinfunction "C_3") (pintype "passive"))
    )
    (net (code "35") (name "Net-(LED1-PadA)") (class "Default")
      (node (ref "LED1") (pin "A") (pinfunction "A_A") (pintype "passive"))
      (node (ref "R13") (pin "2") (pinfunction "2_2") (pintype "passive"))
    )
    (net (code "36") (name "Net-(LED2-PadA)") (class "Default")
      (node (ref "LED2") (pin "A") (pinfunction "A_A") (pintype "passive"))
      (node (ref "R14") (pin "2") (pinfunction "2_2") (pintype "passive"))
    )
    (net (code "37") (name "Net-(Q1-B)") (class "Default")
      (node (ref "Q1") (pin "1") (pinfunction "B_1") (pintype "passive"))
      (node (ref "R7") (pin "2") (pinfunction "2_2") (pintype "passive"))
    )
    (net (code "38") (name "Net-(Q1-C)") (class "Default")
      (node (ref "Q1") (pin "3") (pinfunction "C_3") (pintype "passive"))
      (node (ref "R12") (pin "2") (pinfunction "2_2") (pintype "passive"))
    )
    (net (code "39") (name "Net-(Q4-B)") (class "Default")
      (node (ref "Q4") (pin "1") (pinfunction "B_1") (pintype "passive"))
      (node (ref "R29") (pin "1") (pinfunction "1_1") (pintype "passive"))
    )
    (net (code "40") (name "Net-(Q5-B)") (class "Default")
      (node (ref "Q5") (pin "1") (pinfunction "B_1") (pintype "passive"))
      (node (ref "R53") (pin "2") (pinfunction "2_2") (pintype "passive"))
      (node (ref "R55") (pin "2") (pinfunction "2_2") (pintype "passive"))
    )
    (net (code "41") (name "Net-(Q6-B)") (class "Default")
      (node (ref "Q6") (pin "1") (pinfunction "B_1") (pintype "passive"))
      (node (ref "R54") (pin "2") (pinfunction "2_2") (pintype "passive"))
      (node (ref "R56") (pin "2") (pinfunction "2_2") (pintype "passive"))
    )
    (net (code "42") (name "Net-(R5-Pad1)") (class "Default")
      (node (ref "R5") (pin "1") (pinfunction "1_1") (pintype "passive"))
      (node (ref "USB1") (pin "D+") (pinfunction "D+_D+") (pintype "bidirectional"))
    )
    (net (code "43") (name "Net-(R6-Pad1)") (class "Default")
      (node (ref "R6") (pin "1") (pinfunction "1_1") (pintype "passive"))
      (node (ref "USB1") (pin "D-") (pinfunction "D-_D-") (pintype "bidirectional"))
    )
    (net (code "44") (name "Net-(R31-Pad1)") (class "Default")
      (node (ref "R31") (pin "1") (pinfunction "1_1") (pintype "passive"))
      (node (ref "STMP") (pin "19") (pinfunction "19_19") (pintype "passive"))
    )
    (net (code "45") (name "Net-(R32-Pad1)") (class "Default")
      (node (ref "R32") (pin "1") (pinfunction "1_1") (pintype "passive"))
      (node (ref "STMP") (pin "18") (pinfunction "18_18") (pintype "passive"))
    )
    (net (code "46") (name "Net-(R33-Pad1)") (class "Default")
      (node (ref "R33") (pin "1") (pinfunction "1_1") (pintype "passive"))
      (node (ref "STMP") (pin "17") (pinfunction "17_17") (pintype "passive"))
    )
    (net (code "47") (name "Net-(R34-Pad1)") (class "Default")
      (node (ref "R34") (pin "1") (pinfunction "1_1") (pintype "passive"))
      (node (ref "STMP") (pin "16") (pinfunction "16_16") (pintype "passive"))
    )
    (net (code "48") (name "Net-(R35-Pad1)") (class "Default")
      (node (ref "R35") (pin "1") (pinfunction "1_1") (pintype "passive"))
      (node (ref "STMP") (pin "15") (pinfunction "15_15") (pintype "passive"))
    )
    (net (code "49") (name "Net-(R36-Pad1)") (class "Default")
      (node (ref "R36") (pin "1") (pinfunction "1_1") (pintype "passive"))
      (node (ref "STMP") (pin "14") (pinfunction "14_14") (pintype "passive"))
    )
    (net (code "50") (name "Net-(R37-Pad1)") (class "Default")
      (node (ref "R37") (pin "1") (pinfunction "1_1") (pintype "passive"))
      (node (ref "STMP") (pin "13") (pinfunction "13_13") (pintype "passive"))
    )
    (net (code "51") (name "Net-(R38-Pad1)") (class "Default")
      (node (ref "R38") (pin "1") (pinfunction "1_1") (pintype "passive"))
      (node (ref "STMP") (pin "12") (pinfunction "12_12") (pintype "passive"))
    )
    (net (code "52") (name "Net-(R39-Pad1)") (class "Default")
      (node (ref "R39") (pin "1") (pinfunction "1_1") (pintype "passive"))
      (node (ref "STMP") (pin "10") (pinfunction "10_10") (pintype "passive"))
    )
    (net (code "53") (name "Net-(R40-Pad1)") (class "Default")
      (node (ref "R40") (pin "1") (pinfunction "1_1") (pintype "passive"))
      (node (ref "STMP") (pin "9") (pinfunction "9_9") (pintype "passive"))
    )
    (net (code "54") (name "Net-(R41-Pad1)") (class "Default")
      (node (ref "R41") (pin "1") (pinfunction "1_1") (pintype "passive"))
      (node (ref "STMP") (pin "8") (pinfunction "8_8") (pintype "passive"))
    )
    (net (code "55") (name "Net-(R42-Pad1)") (class "Default")
      (node (ref "R42") (pin "1") (pinfunction "1_1") (pintype "passive"))
      (node (ref "STMP") (pin "7") (pinfunction "7_7") (pintype "passive"))
    )
    (net (code "56") (name "Net-(R43-Pad1)") (class "Default")
      (node (ref "R43") (pin "1") (pinfunction "1_1") (pintype "passive"))
      (node (ref "STMP") (pin "6") (pinfunction "6_6") (pintype "passive"))
    )
    (net (code "57") (name "Net-(R44-Pad1)") (class "Default")
      (node (ref "R44") (pin "1") (pinfunction "1_1") (pintype "passive"))
      (node (ref "STMP") (pin "5") (pinfunction "5_5") (pintype "passive"))
    )
    (net (code "58") (name "Net-(R45-Pad1)") (class "Default")
      (node (ref "R45") (pin "1") (pinfunction "1_1") (pintype "passive"))
      (node (ref "STMP") (pin "4") (pinfunction "4_4") (pintype "passive"))
    )
    (net (code "59") (name "Net-(R46-Pad1)") (class "Default")
      (node (ref "R46") (pin "1") (pinfunction "1_1") (pintype "passive"))
      (node (ref "STMP") (pin "3") (pinfunction "3_3") (pintype "passive"))
    )
    (net (code "60") (name "Net-(SD1-DAT1)") (class "Default")
      (node (ref "R9") (pin "1") (pinfunction "1_1") (pintype "passive"))
      (node (ref "SD1") (pin "8") (pinfunction "DAT1_8") (pintype "bidirectional"))
    )
    (net (code "61") (name "Net-(SD1-DAT2)") (class "Default")
      (node (ref "R11") (pin "1") (pinfunction "1_1") (pintype "passive"))
      (node (ref "SD1") (pin "1") (pinfunction "DAT2_1") (pintype "bidirectional"))
    )
    (net (code "62") (name "Net-(SD1-VDD)") (class "Default")
      (node (ref "C5") (pin "1") (pinfunction "1_1") (pintype "passive"))
      (node (ref "L1") (pin "2") (pinfunction "2_2") (pintype "passive"))
      (node (ref "R11") (pin "2") (pinfunction "2_2") (pintype "passive"))
      (node (ref "R3") (pin "2") (pinfunction "2_2") (pintype "passive"))
      (node (ref "R4") (pin "2") (pinfunction "2_2") (pintype "passive"))
      (node (ref "R9") (pin "2") (pinfunction "2_2") (pintype "passive"))
      (node (ref "SD1") (pin "4") (pinfunction "VDD_4") (pintype "power_in"))
    )
    (net (code "63") (name "Net-(SW2-P)") (class "Default")
      (node (ref "R15") (pin "2") (pinfunction "2_2") (pintype "passive"))
      (node (ref "R17") (pin "2") (pinfunction "2_2") (pintype "passive"))
      (node (ref "SW2") (pin "1") (pinfunction "P_1") (pintype "passive"))
    )
    (net (code "64") (name "Net-(SW3-S)") (class "Default")
      (node (ref "R19") (pin "1") (pinfunction "1_1") (pintype "passive"))
      (node (ref "SW3") (pin "2") (pinfunction "S_2") (pintype "passive"))
    )
    (net (code "65") (name "Net-(SW4-S)") (class "Default")
      (node (ref "R20") (pin "1") (pinfunction "1_1") (pintype "passive"))
      (node (ref "SW4") (pin "2") (pinfunction "S_2") (pintype "passive"))
    )
    (net (code "66") (name "Net-(SW5-S)") (class "Default")
      (node (ref "R21") (pin "1") (pinfunction "1_1") (pintype "passive"))
      (node (ref "SW5") (pin "2") (pinfunction "S_2") (pintype "passive"))
    )
    (net (code "67") (name "Net-(X3A-KL)") (class "Default")
      (node (ref "K1") (pin "O") (pinfunction "O_O") (pintype "passive"))
      (node (ref "X3") (pin "1") (pinfunction "KL_1") (pintype "passive"))
    )
    (net (code "68") (name "Net-(X3B-KL)") (class "Default")
      (node (ref "K1") (pin "P") (pinfunction "P_P") (pintype "passive"))
      (node (ref "X3") (pin "2") (pinfunction "KL_2") (pintype "passive"))
    )
    (net (code "69") (name "Net-(X3C-KL)") (class "Default")
      (node (ref "K1") (pin "S") (pinfunction "S_S") (pintype "passive"))
      (node (ref "X3") (pin "3") (pinfunction "KL_3") (pintype "passive"))
    )
    (net (code "70") (name "Net-(X3D-KL)") (class "Default")
      (node (ref "K2") (pin "O") (pinfunction "O_O") (pintype "passive"))
      (node (ref "X3") (pin "4") (pinfunction "KL_4") (pintype "passive"))
    )
    (net (code "71") (name "Net-(X3E-KL)") (class "Default")
      (node (ref "K2") (pin "P") (pinfunction "P_P") (pintype "passive"))
      (node (ref "X3") (pin "5") (pinfunction "KL_5") (pintype "passive"))
    )
    (net (code "72") (name "Net-(X3F-KL)") (class "Default")
      (node (ref "K2") (pin "S") (pinfunction "S_S") (pintype "passive"))
      (node (ref "X3") (pin "6") (pinfunction "KL_6") (pintype "passive"))
    )
    (net (code "73") (name "OSC32_IN") (class "Default")
      (node (ref "C8") (pin "1") (pinfunction "1_1") (pintype "passive"))
      (node (ref "IC2") (pin "3") (pinfunction "PC14/OSC32_IN_3") (pintype "bidirectional"))
      (node (ref "Q2") (pin "2") (pinfunction "2_2") (pintype "passive"))
    )
    (net (code "74") (name "OSC32_OUT") (class "Default")
      (node (ref "C9") (pin "1") (pinfunction "1_1") (pintype "passive"))
      (node (ref "IC2") (pin "4") (pinfunction "PC15/OSC32_OUT_4") (pintype "bidirectional"))
      (node (ref "Q2") (pin "1") (pinfunction "1_1") (pintype "passive"))
    )
    (net (code "75") (name "OSC_IN") (class "Default")
      (node (ref "C10") (pin "1") (pinfunction "1_1") (pintype "passive"))
      (node (ref "IC2") (pin "5") (pinfunction "OSC_IN/(PD0/CANRX)_5") (pintype "input"))
      (node (ref "Q3") (pin "1") (pinfunction "1_1") (pintype "passive"))
      (node (ref "R22") (pin "2") (pinfunction "2_2") (pintype "passive"))
    )
    (net (code "76") (name "OSC_OUT") (class "Default")
      (node (ref "C11") (pin "1") (pinfunction "1_1") (pintype "passive"))
      (node (ref "IC2") (pin "6") (pinfunction "OSC_OUT/(PD1/CANTX)_6") (pintype "output"))
      (node (ref "Q3") (pin "2") (pinfunction "2_2") (pintype "passive"))
      (node (ref "R22") (pin "1") (pinfunction "1_1") (pintype "passive"))
    )
    (net (code "77") (name "PA0") (class "Default")
      (node (ref "C7") (pin "2") (pinfunction "2_2") (pintype "passive"))
      (node (ref "IC2") (pin "14") (pinfunction "PA0/WKUP/USART2_CTS/ADC12_IN0/TIM2_CH1_ETR_14") (pintype "bidirectional"))
      (node (ref "R19") (pin "2") (pinfunction "2_2") (pintype "passive"))
      (node (ref "R20") (pin "2") (pinfunction "2_2") (pintype "passive"))
      (node (ref "R21") (pin "2") (pinfunction "2_2") (pintype "passive"))
      (node (ref "R23") (pin "2") (pinfunction "2_2") (pintype "passive"))
      (node (ref "STMP") (pin "39") (pinfunction "19_39") (pintype "passive"))
    )
    (net (code "78") (name "PA1") (class "Default")
      (node (ref "IC2") (pin "15") (pinfunction "PA1/USART2_RTS/ADC12_IN1/TIM2_CH2_15") (pintype "bidirectional"))
      (node (ref "R26") (pin "1") (pinfunction "1_1") (pintype "passive"))
      (node (ref "STMP") (pin "38") (pinfunction "18_38") (pintype "passive"))
    )
    (net (code "79") (name "PA2") (class "Default")
      (node (ref "IC2") (pin "16") (pinfunction "PA2/USART2_TX/ADC12_IN2/TIM2_CH3_16") (pintype "bidirectional"))
      (node (ref "R24") (pin "1") (pinfunction "1_1") (pintype "passive"))
      (node (ref "STMP") (pin "37") (pinfunction "17_37") (pintype "passive"))
    )
    (net (code "80") (name "PA3") (class "Default")
      (node (ref "IC2") (pin "17") (pinfunction "PA3/USART2_RX/ADC12_IN3/TIM2_CH4_17") (pintype "bidirectional"))
      (node (ref "STMP") (pin "36") (pinfunction "16_36") (pintype "passive"))
    )
    (net (code "81") (name "PA4") (class "Default")
      (node (ref "IC2") (pin "20") (pinfunction "PA4/SPI1_NSS/ADC12_IN4/USART2_CK_20") (pintype "bidirectional"))
      (node (ref "R25") (pin "1") (pinfunction "1_1") (pintype "passive"))
      (node (ref "STMP") (pin "35") (pinfunction "15_35") (pintype "passive"))
    )
    (net (code "82") (name "PA5") (class "Default")
      (node (ref "IC2") (pin "21") (pinfunction "PA5/SPI1_SCK/ADC12_IN5_21") (pintype "bidirectional"))
      (node (ref "STMP") (pin "34") (pinfunction "14_34") (pintype "passive"))
    )
    (net (code "83") (name "PA6") (class "Default")
      (node (ref "IC2") (pin "22") (pinfunction "PA6/SPI1_MISO/ADC12_IN6/TIM3_CH1_22") (pintype "bidirectional"))
      (node (ref "STMP") (pin "33") (pinfunction "13_33") (pintype "passive"))
    )
    (net (code "84") (name "PA7") (class "Default")
      (node (ref "IC2") (pin "23") (pinfunction "PA7SPI1_MOSI/ADC12_IN7/TIM3_CH2_23") (pintype "bidirectional"))
      (node (ref "STMP") (pin "32") (pinfunction "12_32") (pintype "passive"))
    )
    (net (code "85") (name "PA8") (class "Default")
      (node (ref "IC2") (pin "41") (pinfunction "PA8/USART1_CK/MCO/TIM1_CH1_41") (pintype "bidirectional"))
      (node (ref "STMP") (pin "25") (pinfunction "5_25") (pintype "passive"))
    )
    (net (code "86") (name "PA15") (class "Default")
      (node (ref "IC2") (pin "50") (pinfunction "JTDI/(TIM2_CH1_ETR/PA15/SPI1_NSS)_50") (pintype "bidirectional"))
      (node (ref "STMP") (pin "24") (pinfunction "4_24") (pintype "passive"))
    )
    (net (code "87") (name "PB0") (class "Default")
      (node (ref "IC2") (pin "26") (pinfunction "PB0/ADC12_IN8/TIM3_CH3/(TIM1_CH2N)_26") (pintype "bidirectional"))
      (node (ref "R45") (pin "2") (pinfunction "2_2") (pintype "passive"))
    )
    (net (code "88") (name "PB1") (class "Default")
      (node (ref "IC2") (pin "27") (pinfunction "PB1/ADC12_IN9/TIM3_CH4/(TIM1_CH3N)_27") (pintype "bidirectional"))
      (node (ref "R46") (pin "2") (pinfunction "2_2") (pintype "passive"))
    )
    (net (code "89") (name "PB3") (class "Default")
      (node (ref "IC2") (pin "55") (pinfunction "JTDO/(TIM2_CH2/PB3/TRACESWO/SPI1_SCK)_55") (pintype "bidirectional"))
      (node (ref "STMP") (pin "23") (pinfunction "3_23") (pintype "passive"))
    )
    (net (code "90") (name "PB4") (class "Default")
      (node (ref "IC2") (pin "56") (pinfunction "JTNRST/(PB4/TIM3_CH1/SPI1_MISO)_56") (pintype "bidirectional"))
      (node (ref "R29") (pin "2") (pinfunction "2_2") (pintype "passive"))
    )
    (net (code "91") (name "PC0") (class "Default")
      (node (ref "IC2") (pin "8") (pinfunction "PC0/ADC10_8") (pintype "bidirectional"))
      (node (ref "R39") (pin "2") (pinfunction "2_2") (pintype "passive"))
    )
    (net (code "92") (name "PC1") (class "Default")
      (node (ref "IC2") (pin "9") (pinfunction "PC1/ADC11_9") (pintype "bidirectional"))
      (node (ref "R40") (pin "2") (pinfunction "2_2") (pintype "passive"))
    )
    (net (code "93") (name "PC2") (class "Default")
      (node (ref "IC2") (pin "10") (pinfunction "PC2/ADC12_10") (pintype "bidirectional"))
      (node (ref "R41") (pin "2") (pinfunction "2_2") (pintype "passive"))
    )
    (net (code "94") (name "PC3") (class "Default")
      (node (ref "IC2") (pin "11") (pinfunction "PC3/ADC13_11") (pintype "bidirectional"))
      (node (ref "R42") (pin "2") (pinfunction "2_2") (pintype "passive"))
    )
    (net (code "95") (name "PC4") (class "Default")
      (node (ref "IC2") (pin "24") (pinfunction "PC4/ADC14_24") (pintype "bidirectional"))
      (node (ref "R43") (pin "2") (pinfunction "2_2") (pintype "passive"))
    )
    (net (code "96") (name "PC5") (class "Default")
      (node (ref "IC2") (pin "25") (pinfunction "PC5/ADC15_25") (pintype "bidirectional"))
      (node (ref "R44") (pin "2") (pinfunction "2_2") (pintype "passive"))
    )
    (net (code "97") (name "PC13") (class "Default")
      (node (ref "IC2") (pin "2") (pinfunction "PC13/TAMPER-RTC_2") (pintype "bidirectional"))
      (node (ref "STMP") (pin "22") (pinfunction "2_22") (pintype "passive"))
    )
    (net (code "98") (name "RS485_A") (class "Default")
      (node (ref "F2") (pin "P$2") (pinfunction "2_P$2") (pintype "passive"))
      (node (ref "X1") (pin "2") (pinfunction "SK_2") (pintype "passive"))
    )
    (net (code "99") (name "RS485_B") (class "Default")
      (node (ref "F1") (pin "P$2") (pinfunction "2_P$2") (pintype "passive"))
      (node (ref "X1") (pin "1") (pinfunction "SK_1") (pintype "passive"))
    )
    (net (code "100") (name "RXD1") (class "Default")
      (node (ref "IC2") (pin "43") (pinfunction "PA10/USART1_RX/TIM1_CH3_43") (pintype "bidirectional"))
      (node (ref "JP1") (pin "3") (pinfunction "3_3") (pintype "passive"))
      (node (ref "R30") (pin "1") (pinfunction "1_1") (pintype "passive"))
    )
    (net (code "101") (name "RXD3") (class "Default")
      (node (ref "IC2") (pin "52") (pinfunction "PC11/(USART3_RX)_52") (pintype "bidirectional"))
      (node (ref "IC3") (pin "1") (pinfunction "RO_1") (pintype "output"))
    )
    (net (code "102") (name "SCL2") (class "Default")
      (node (ref "IC1") (pin "6") (pinfunction "SCL_6") (pintype "bidirectional"))
      (node (ref "IC2") (pin "29") (pinfunction "PB10/I2C2_SCL/USART3_TX/(TIM2_CH3)_29") (pintype "bidirectional"))
      (node (ref "R8") (pin "1") (pinfunction "1_1") (pintype "passive"))
      (node (ref "STMP") (pin "31") (pinfunction "11_31") (pintype "passive"))
    )
    (net (code "103") (name "SDA2") (class "Default")
      (node (ref "IC1") (pin "5") (pinfunction "SDA_5") (pintype "bidirectional"))
      (node (ref "IC2") (pin "30") (pinfunction "PB11/I2C2_SDA/USART3_RX/(TIM2_CH4)_30") (pintype "bidirectional"))
      (node (ref "R10") (pin "1") (pinfunction "1_1") (pintype "passive"))
      (node (ref "STMP") (pin "30") (pinfunction "10_30") (pintype "passive"))
    )
    (net (code "104") (name "SPI2_MISO") (class "Default")
      (node (ref "IC2") (pin "35") (pinfunction "PB14/SPI2_MISO/TIM1_CH2N/USART3_RTS_35") (pintype "bidirectional"))
      (node (ref "SD1") (pin "7") (pinfunction "DAT0(DO)_7") (pintype "bidirectional"))
      (node (ref "STMP") (pin "27") (pinfunction "7_27") (pintype "passive"))
    )
    (net (code "105") (name "SPI2_MOSI") (class "Default")
      (node (ref "IC2") (pin "36") (pinfunction "PB15/SPI2_MOSI/TIM1_CH3N_36") (pintype "bidirectional"))
      (node (ref "SD1") (pin "3") (pinfunction "CMD(DI)_3") (pintype "bidirectional"))
      (node (ref "STMP") (pin "26") (pinfunction "6_26") (pintype "passive"))
    )
    (net (code "106") (name "SPI2_NSS") (class "Default")
      (node (ref "IC2") (pin "33") (pinfunction "PB12/SPI2_NSS/I2C2_SMBAI/TIM1_BKIN/USART3_CK_33") (pintype "bidirectional"))
      (node (ref "STMP") (pin "29") (pinfunction "9_29") (pintype "passive"))
    )
    (net (code "107") (name "SPI2_SCLK") (class "Default")
      (node (ref "IC2") (pin "34") (pinfunction "PB13/SPI2_SCK/TIM1_CH1N/USART3_CTS_34") (pintype "bidirectional"))
      (node (ref "SD1") (pin "5") (pinfunction "CLK(SCLK)_5") (pintype "input"))
      (node (ref "STMP") (pin "28") (pinfunction "8_28") (pintype "passive"))
    )
    (net (code "108") (name "SWCLK") (class "Default")
      (node (ref "IC2") (pin "49") (pinfunction "JTCK-SWCLK/(PA14)_49") (pintype "bidirectional"))
      (node (ref "R1") (pin "1") (pinfunction "1_1") (pintype "passive"))
      (node (ref "SWD1") (pin "2") (pinfunction "2_2") (pintype "passive"))
    )
    (net (code "109") (name "SWDIO") (class "Default")
      (node (ref "IC2") (pin "46") (pinfunction "JTMS-SWDIO/(PA13)_46") (pintype "bidirectional"))
      (node (ref "R2") (pin "1") (pinfunction "1_1") (pintype "passive"))
      (node (ref "SWD1") (pin "4") (pinfunction "4_4") (pintype "passive"))
    )
    (net (code "110") (name "TIM3_CH1") (class "Default")
      (node (ref "IC2") (pin "37") (pinfunction "PC6/(TIM3_CH1)_37") (pintype "bidirectional"))
      (node (ref "R31") (pin "2") (pinfunction "2_2") (pintype "passive"))
    )
    (net (code "111") (name "TIM3_CH2") (class "Default")
      (node (ref "IC2") (pin "38") (pinfunction "PC7/(TIM3_CH2)_38") (pintype "bidirectional"))
      (node (ref "R32") (pin "2") (pinfunction "2_2") (pintype "passive"))
    )
    (net (code "112") (name "TIM3_CH3") (class "Default")
      (node (ref "IC2") (pin "39") (pinfunction "PC8/(TIM3_CH3)_39") (pintype "bidirectional"))
      (node (ref "R33") (pin "2") (pinfunction "2_2") (pintype "passive"))
    )
    (net (code "113") (name "TIM3_CH4") (class "Default")
      (node (ref "IC2") (pin "40") (pinfunction "PC9/(TIM3_CH4)_40") (pintype "bidirectional"))
      (node (ref "R34") (pin "2") (pinfunction "2_2") (pintype "passive"))
    )
    (net (code "114") (name "TIM4_CH1") (class "Default")
      (node (ref "IC2") (pin "58") (pinfunction "PB6/I2C1_SCL/TIM4_CH1/(USART1_TX)_58") (pintype "bidirectional"))
      (node (ref "R35") (pin "2") (pinfunction "2_2") (pintype "passive"))
    )
    (net (code "115") (name "TIM4_CH2") (class "Default")
      (node (ref "IC2") (pin "59") (pinfunction "PB7/I2C1_SDA/TIM4_CH2/(USART1_RX)_59") (pintype "bidirectional"))
      (node (ref "R36") (pin "2") (pinfunction "2_2") (pintype "passive"))
    )
    (net (code "116") (name "TIM4_CH3") (class "Default")
      (node (ref "IC2") (pin "61") (pinfunction "PB8/TIM4_CH3/(I2C1_SCL/CANRX)_61") (pintype "bidirectional"))
      (node (ref "R37") (pin "2") (pinfunction "2_2") (pintype "passive"))
    )
    (net (code "117") (name "TIM4_CH4") (class "Default")
      (node (ref "IC2") (pin "62") (pinfunction "PB9/TIM4_CH4/(I2C1_SDA/CANTX)_62") (pintype "bidirectional"))
      (node (ref "R38") (pin "2") (pinfunction "2_2") (pintype "passive"))
    )
    (net (code "118") (name "TXD1") (class "Default")
      (node (ref "IC2") (pin "42") (pinfunction "PA9/USART1_TX/TIM1_CH2_42") (pintype "bidirectional"))
      (node (ref "JP1") (pin "2") (pinfunction "2_2") (pintype "passive"))
    )
    (net (code "119") (name "TXD3") (class "Default")
      (node (ref "IC2") (pin "51") (pinfunction "PC10/(USART3_TX)_51") (pintype "bidirectional"))
      (node (ref "IC3") (pin "2") (pinfunction "RE/_2") (pintype "input"))
      (node (ref "IC3") (pin "3") (pinfunction "DE_3") (pintype "input"))
      (node (ref "R47") (pin "2") (pinfunction "2_2") (pintype "passive"))
    )
    (net (code "120") (name "USB_DM") (class "Default")
      (node (ref "C3") (pin "1") (pinfunction "1_1") (pintype "passive"))
      (node (ref "IC2") (pin "44") (pinfunction "PA11/CANRX/USBDM/USART1_CTS/TIM1_CH4_44") (pintype "bidirectional"))
      (node (ref "R6") (pin "2") (pinfunction "2_2") (pintype "passive"))
    )
    (net (code "121") (name "USB_DP") (class "Default")
      (node (ref "C4") (pin "1") (pinfunction "1_1") (pintype "passive"))
      (node (ref "IC2") (pin "45") (pinfunction "PA12/CANTX/USBDP/USART1_RTS/TIM1_ETR_45") (pintype "bidirectional"))
      (node (ref "R12") (pin "1") (pinfunction "1_1") (pintype "passive"))
      (node (ref "R5") (pin "2") (pinfunction "2_2") (pintype "passive"))
    )
    (net (code "122") (name "VBAT") (class "Default")
      (node (ref "G1") (pin "+") (pinfunction "+_+") (pintype "passive"))
      (node (ref "IC2") (pin "1") (pinfunction "VBAT_1") (pintype "power_in"))
    )
    (net (code "123") (name "VDDA") (class "Default")
      (node (ref "C15") (pin "1") (pinfunction "1_1") (pintype "passive"))
      (node (ref "C7") (pin "1") (pinfunction "1_1") (pintype "passive"))
      (node (ref "IC2") (pin "13") (pinfunction "VDDA_13") (pintype "power_in"))
      (node (ref "L2") (pin "2") (pinfunction "2_2") (pintype "passive"))
      (node (ref "SW3") (pin "1") (pinfunction "P_1") (pintype "passive"))
      (node (ref "SW4") (pin "1") (pinfunction "P_1") (pintype "passive"))
      (node (ref "SW5") (pin "1") (pinfunction "P_1") (pintype "passive"))
    )
    (net (code "124") (name "unconnected-(SWD1-Pad6)") (class "Default")
      (node (ref "SWD1") (pin "6") (pinfunction "6_6") (pintype "passive"))
    )
    (net (code "125") (name "unconnected-(U1-MASS-Pad4)") (class "Default")
      (node (ref "U1") (pin "4") (pinfunction "MASS_4") (pintype "passive"))
    )
    (net (code "126") (name "unconnected-(U2-MASS-Pad4)") (class "Default")
      (node (ref "U2") (pin "4") (pinfunction "MASS_4") (pintype "passive"))
    )
    (net (code "127") (name "~{LCD_CS}") (class "Default")
      (node (ref "LCD1") (pin "2") (pinfunction "~{CS}_2") (pintype "input"))
      (node (ref "R26") (pin "2") (pinfunction "2_2") (pintype "passive"))
      (node (ref "R27") (pin "1") (pinfunction "1_1") (pintype "passive"))
    )
    (net (code "128") (name "~{RESET}") (class "Default")
      (node (ref "C6") (pin "1") (pinfunction "1_1") (pintype "passive"))
      (node (ref "IC2") (pin "7") (pinfunction "~{RESET}_7") (pintype "input"))
      (node (ref "LCD1") (pin "1") (pinfunction "~{RST}_1") (pintype "input"))
      (node (ref "R18") (pin "1") (pinfunction "1_1") (pintype "passive"))
      (node (ref "SW1") (pin "2") (pinfunction "S_2") (pintype "passive"))
      (node (ref "SWD1") (pin "5") (pinfunction "5_5") (pintype "passive"))
    )
    (net (code "129") (name "~{SD_CS}") (class "Default")
      (node (ref "IC2") (pin "54") (pinfunction "PD2/TIM3_ETR_54") (pintype "bidirectional"))
      (node (ref "R3") (pin "1") (pinfunction "1_1") (pintype "passive"))
      (node (ref "SD1") (pin "2") (pinfunction "CD/DAT3(~{CS})_2") (pintype "bidirectional"))
    )
    (net (code "130") (name "~{SD_DET}") (class "Default")
      (node (ref "R4") (pin "1") (pinfunction "1_1") (pintype "passive"))
      (node (ref "SD1") (pin "9") (pinfunction "~{CARD}_9") (pintype "passive"))
    )
    (net (code "131") (name "~{USB_DIS}") (class "Default")
      (node (ref "IC2") (pin "57") (pinfunction "PB5/I2C1_SMBA/(TIM3_CH2/SPI1_MOSI)_57") (pintype "bidirectional"))
      (node (ref "R7") (pin "1") (pinfunction "1_1") (pintype "passive"))
    )
  )
)
